# REG5-3_3.net
KiCad netlist of a schematic drawn in Altium Designer
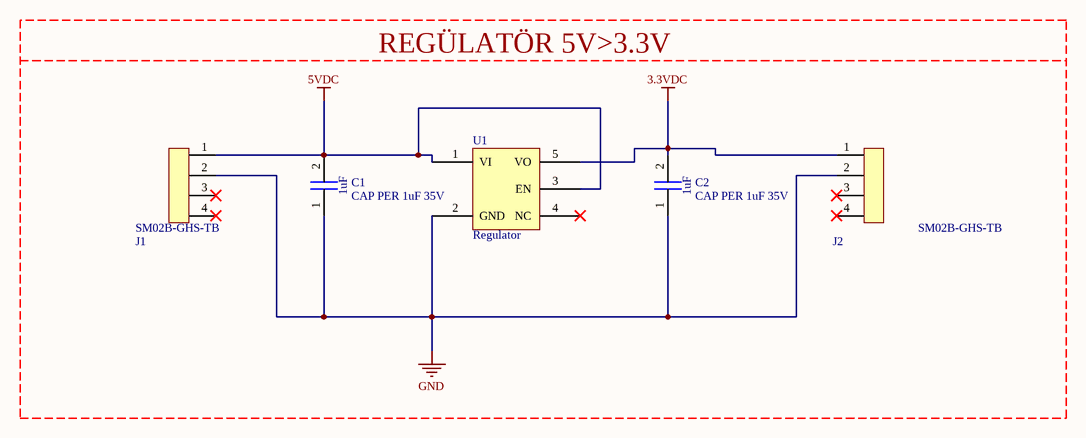
[diagram p0: REG5-3.3.SchDoc]

(export (version "E")
  (design (tool "Eeschema 10.0.6"))
  (components
    (comp (ref "C1")
      (value "CAP PER 1uF 35V")
      (footprint "CAP_0805")
      (fields
        (field (name "MANUFACTURER") "Vishay")
        (field (name "MANUFACTURER PART NUMBER") "T58W9105M035C0500")
      )
      (libsource (lib "Schlib1") (part "CAP PER 1uF 35V"))
    )
    (comp (ref "C2")
      (value "CAP PER 1uF 35V")
      (footprint "CAP_0805")
      (fields
        (field (name "MANUFACTURER") "Vishay")
        (field (name "MANUFACTURER PART NUMBER") "T58W9105M035C0500")
      )
      (libsource (lib "Schlib1") (part "CAP PER 1uF 35V"))
    )
    (comp (ref "J1")
      (value "SM02B-GHS-TB")
      (footprint "SM02B-GHS-TB(LF)(SN)")
      (description "Conn Shrouded Header HDR 2 POS 1.25mm Solder RA Side Entry SMD T/R")
      (fields
        (field (name "MANUFACTURER") "JST")
        (field (name "MANUFACTURER PART NUMBER") "SM02B-GHS-TB(LF)(SN)")
      )
      (libsource (lib "Schlib1") (part "SM02B-GHS-TB"))
    )
    (comp (ref "J2")
      (value "SM02B-GHS-TB")
      (footprint "SM02B-GHS-TB(LF)(SN)")
      (description "Conn Shrouded Header HDR 2 POS 1.25mm Solder RA Side Entry SMD T/R")
      (fields
        (field (name "MANUFACTURER") "JST")
        (field (name "MANUFACTURER PART NUMBER") "SM02B-GHS-TB(LF)(SN)")
      )
      (libsource (lib "") (part "SM02B-GHS-TB_1"))
    )
    (comp (ref "U1")
      (value "Regulator")
      (footprint "SOT23-5")
      (description "Fixed LDO Voltage Regulator, 2.5V to 6V, 155mV drop, 3.3V/150mA out, SOT-23-5")
      (fields
        (field (name "MANUFACTURER") "Microchip")
        (field (name "MANUFACTURER PART NUMBER") "MIC5317-3.3YM5-TR")
      )
      (libsource (lib "Schlib1") (part "MIC5317-3.3YM5-TR"))
    )
  )
  (nets
    (net (code "1") (name "3.3VDC") (class "Default")
      (node (ref "C2") (pin "2") (pintype "passive"))
      (node (ref "J2") (pin "1") (pinfunction "1_1") (pintype "passive"))
      (node (ref "U1") (pin "5") (pinfunction "VO_5") (pintype "passive"))
    )
    (net (code "2") (name "5VDC") (class "Default")
      (node (ref "C1") (pin "2") (pintype "passive"))
      (node (ref "J1") (pin "1") (pinfunction "1_1") (pintype "passive"))
      (node (ref "U1") (pin "1") (pinfunction "VI_1") (pintype "passive"))
      (node (ref "U1") (pin "3") (pinfunction "EN_3") (pintype "passive"))
    )
    (net (code "3") (name "GND") (class "Default")
      (node (ref "C1") (pin "1") (pintype "passive"))
      (node (ref "C2") (pin "1") (pintype "passive"))
      (node (ref "J1") (pin "2") (pinfunction "2_2") (pintype "passive"))
      (node (ref "J2") (pin "2") (pinfunction "2_2") (pintype "passive"))
      (node (ref "U1") (pin "2") (pinfunction "GND_2") (pintype "passive"))
    )
    (net (code "4") (name "unconnected-(J1-Pad3)") (class "Default")
      (node (ref "J1") (pin "3") (pinfunction "3_3") (pintype "passive+no_connect"))
    )
    (net (code "5") (name "unconnected-(J1-Pad4)") (class "Default")
      (node (ref "J1") (pin "4") (pintype "passive+no_connect"))
    )
    (net (code "6") (name "unconnected-(J2-Pad3)") (class "Default")
      (node (ref "J2") (pin "3") (pinfunction "3_3") (pintype "passive+no_connect"))
    )
    (net (code "7") (name "unconnected-(J2-Pad4)") (class "Default")
      (node (ref "J2") (pin "4") (pintype "passive+no_connect"))
    )
    (net (code "8") (name "unconnected-(U1-NC-Pad4)") (class "Default")
      (node (ref "U1") (pin "4") (pinfunction "NC_4") (pintype "passive+no_connect"))
    )
  )
)
